# GeneralPurposePowerSupply.net
KiCad netlist of a schematic drawn in Altium Designer
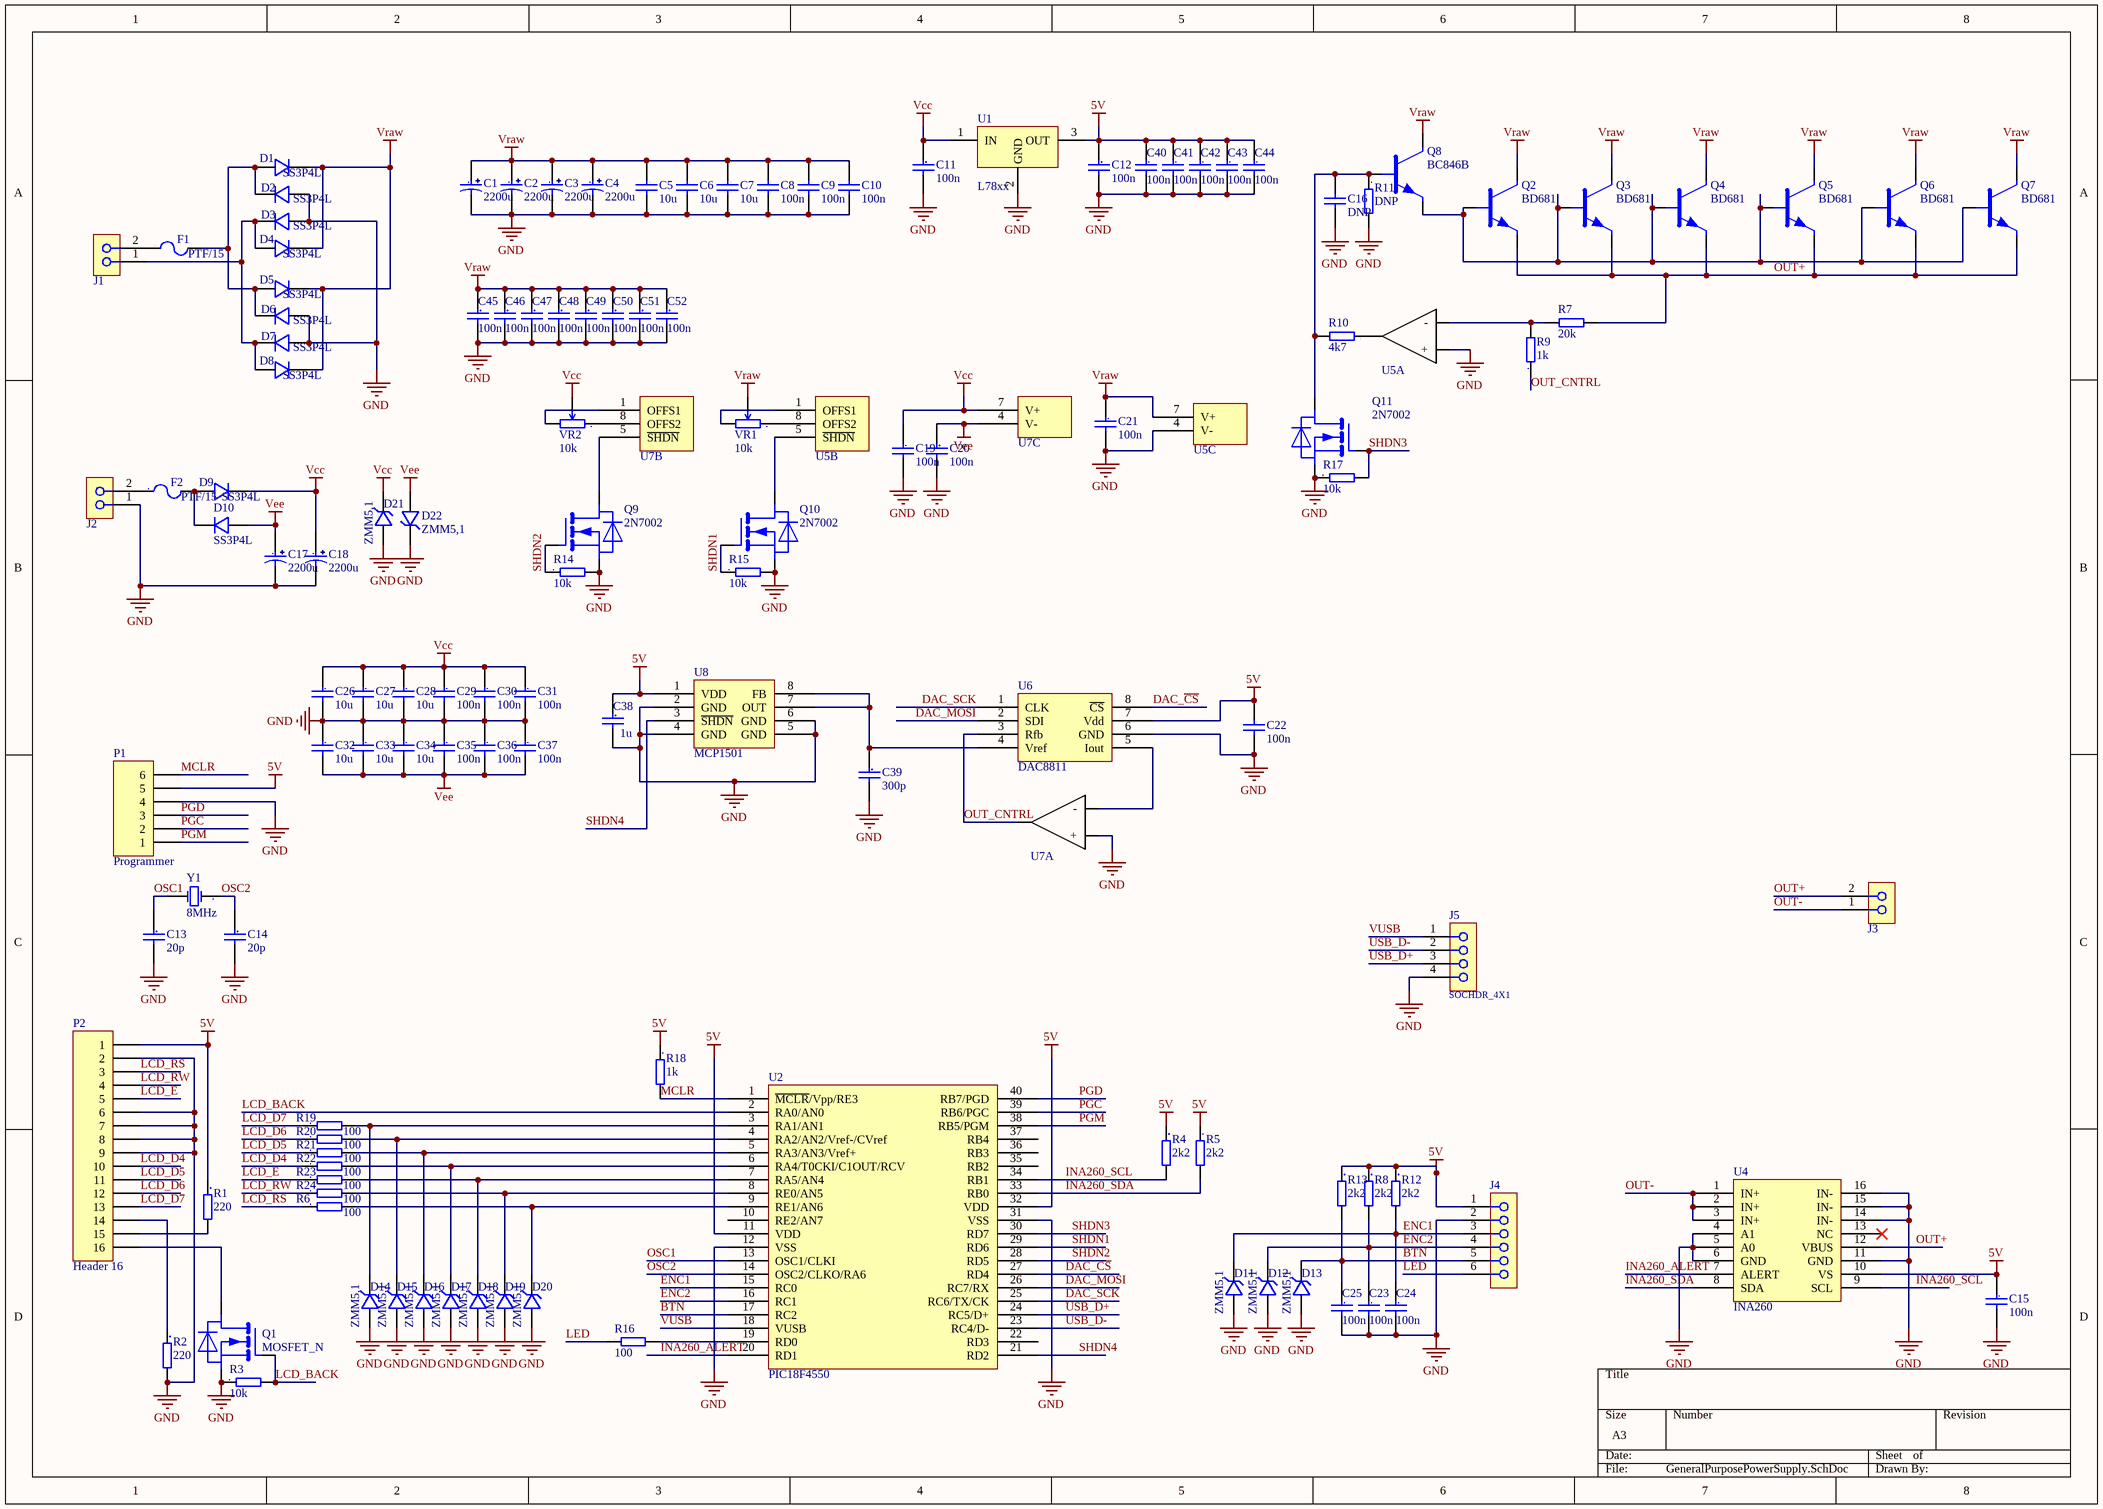
[diagram p0: GeneralPurposePowerSupply.SchDoc]

(export (version "E")
  (design (tool "Eeschema 10.0.6"))
  (components
    (comp (ref "C1") (value "2200u") (footprint "C_16x32") (libsource (lib "MyLib") (part "CAP_POL")))
    (comp (ref "C2") (value "2200u") (footprint "C_16x32") (libsource (lib "MyLib") (part "CAP_POL")))
    (comp (ref "C3") (value "2200u") (footprint "C_16x32") (libsource (lib "MyLib") (part "CAP_POL")))
    (comp (ref "C4") (value "2200u") (footprint "C_16x32") (libsource (lib "MyLib") (part "CAP_POL")))
    (comp (ref "C5") (value "10u") (footprint "C0805_N") (libsource (lib "MyLib") (part "CAP")))
    (comp (ref "C6") (value "10u") (footprint "C0805_N") (libsource (lib "MyLib") (part "CAP")))
    (comp (ref "C7") (value "10u") (footprint "C0805_N") (libsource (lib "MyLib") (part "CAP")))
    (comp (ref "C8") (value "100n") (footprint "C0603_N") (libsource (lib "MyLib") (part "CAP")))
    (comp (ref "C9") (value "100n") (footprint "C0603_N") (libsource (lib "MyLib") (part "CAP")))
    (comp (ref "C10") (value "100n") (footprint "C0603_N") (libsource (lib "MyLib") (part "CAP")))
    (comp (ref "C11") (value "100n") (footprint "C0603_N") (libsource (lib "MyLib") (part "CAP")))
    (comp (ref "C12") (value "100n") (footprint "C0603_N") (libsource (lib "MyLib") (part "CAP")))
    (comp (ref "C13") (value "20p") (footprint "C0603_N") (libsource (lib "MyLib") (part "CAP")))
    (comp (ref "C14") (value "20p") (footprint "C0603_N") (libsource (lib "MyLib") (part "CAP")))
    (comp (ref "C15") (value "100n") (footprint "C0603_N") (libsource (lib "MyLib") (part "CAP")))
    (comp (ref "C16") (value "DNP") (footprint "C0603_N") (libsource (lib "MyLib") (part "CAP")))
    (comp (ref "C17") (value "2200u") (footprint "C_16x32") (libsource (lib "MyLib") (part "CAP_POL")))
    (comp (ref "C18") (value "2200u") (footprint "C_16x32") (libsource (lib "MyLib") (part "CAP_POL")))
    (comp (ref "C19") (value "100n") (footprint "C0603_N") (libsource (lib "MyLib") (part "CAP")))
    (comp (ref "C20") (value "100n") (footprint "C0603_N") (libsource (lib "MyLib") (part "CAP")))
    (comp (ref "C21") (value "100n") (footprint "C0603_N") (libsource (lib "MyLib") (part "CAP")))
    (comp (ref "C22") (value "100n") (footprint "C0603_N") (libsource (lib "MyLib") (part "CAP")))
    (comp (ref "C23") (value "100n") (footprint "C0603_N") (libsource (lib "MyLib") (part "CAP")))
    (comp (ref "C24") (value "100n") (footprint "C0603_N") (libsource (lib "MyLib") (part "CAP")))
    (comp (ref "C25") (value "100n") (footprint "C0603_N") (libsource (lib "MyLib") (part "CAP")))
    (comp (ref "C26") (value "10u") (footprint "C0805_N") (libsource (lib "MyLib") (part "CAP")))
    (comp (ref "C27") (value "10u") (footprint "C0805_N") (libsource (lib "MyLib") (part "CAP")))
    (comp (ref "C28") (value "10u") (footprint "C0805_N") (libsource (lib "MyLib") (part "CAP")))
    (comp (ref "C29") (value "100n") (footprint "C0603_N") (libsource (lib "MyLib") (part "CAP")))
    (comp (ref "C30") (value "100n") (footprint "C0603_N") (libsource (lib "MyLib") (part "CAP")))
    (comp (ref "C31") (value "100n") (footprint "C0603_N") (libsource (lib "MyLib") (part "CAP")))
    (comp (ref "C32") (value "10u") (footprint "C0805_N") (libsource (lib "MyLib") (part "CAP")))
    (comp (ref "C33") (value "10u") (footprint "C0805_N") (libsource (lib "MyLib") (part "CAP")))
    (comp (ref "C34") (value "10u") (footprint "C0805_N") (libsource (lib "MyLib") (part "CAP")))
    (comp (ref "C35") (value "100n") (footprint "C0603_N") (libsource (lib "MyLib") (part "CAP")))
    (comp (ref "C36") (value "100n") (footprint "C0603_N") (libsource (lib "MyLib") (part "CAP")))
    (comp (ref "C37") (value "100n") (footprint "C0603_N") (libsource (lib "MyLib") (part "CAP")))
    (comp (ref "C38") (value "1u") (footprint "C0603_N") (libsource (lib "MyLib") (part "CAP")))
    (comp (ref "C39") (value "300p") (footprint "C0603_N") (libsource (lib "MyLib") (part "CAP")))
    (comp (ref "C40") (value "100n") (footprint "C0603_N") (libsource (lib "MyLib") (part "CAP")))
    (comp (ref "C41") (value "100n") (footprint "C0603_N") (libsource (lib "MyLib") (part "CAP")))
    (comp (ref "C42") (value "100n") (footprint "C0603_N") (libsource (lib "MyLib") (part "CAP")))
    (comp (ref "C43") (value "100n") (footprint "C0603_N") (libsource (lib "MyLib") (part "CAP")))
    (comp (ref "C44") (value "100n") (footprint "C0603_N") (libsource (lib "MyLib") (part "CAP")))
    (comp (ref "C45") (value "100n") (footprint "C0603_N") (libsource (lib "MyLib") (part "CAP")))
    (comp (ref "C46") (value "100n") (footprint "C0603_N") (libsource (lib "MyLib") (part "CAP")))
    (comp (ref "C47") (value "100n") (footprint "C0603_N") (libsource (lib "MyLib") (part "CAP")))
    (comp (ref "C48") (value "100n") (footprint "C0603_N") (libsource (lib "MyLib") (part "CAP")))
    (comp (ref "C49") (value "100n") (footprint "C0603_N") (libsource (lib "MyLib") (part "CAP")))
    (comp (ref "C50") (value "100n") (footprint "C0603_N") (libsource (lib "MyLib") (part "CAP")))
    (comp (ref "C51") (value "100n") (footprint "C0603_N") (libsource (lib "MyLib") (part "CAP")))
    (comp (ref "C52") (value "100n") (footprint "C0603_N") (libsource (lib "MyLib") (part "CAP")))
    (comp (ref "D1") (value "SS3P4L") (footprint "TO-277") (libsource (lib "MyLib") (part "DIODE")))
    (comp (ref "D2") (value "SS3P4L") (footprint "TO-277") (libsource (lib "MyLib") (part "DIODE")))
    (comp (ref "D3") (value "SS3P4L") (footprint "TO-277") (libsource (lib "MyLib") (part "DIODE")))
    (comp (ref "D4") (value "SS3P4L") (footprint "TO-277") (libsource (lib "MyLib") (part "DIODE")))
    (comp (ref "D5") (value "SS3P4L") (footprint "TO-277") (libsource (lib "MyLib") (part "DIODE")))
    (comp (ref "D6") (value "SS3P4L") (footprint "TO-277") (libsource (lib "MyLib") (part "DIODE")))
    (comp (ref "D7") (value "SS3P4L") (footprint "TO-277") (libsource (lib "MyLib") (part "DIODE")))
    (comp (ref "D8") (value "SS3P4L") (footprint "TO-277") (libsource (lib "MyLib") (part "DIODE")))
    (comp (ref "D9") (value "SS3P4L") (footprint "TO-277") (libsource (lib "MyLib") (part "DIODE")))
    (comp (ref "D10") (value "SS3P4L") (footprint "TO-277") (libsource (lib "MyLib") (part "DIODE")))
    (comp (ref "D11") (value "ZMM5,1") (footprint "SOD-80") (libsource (lib "MyLib") (part "DIODE_ZENER")))
    (comp (ref "D12") (value "ZMM5,1") (footprint "SOD-80") (libsource (lib "MyLib") (part "DIODE_ZENER")))
    (comp (ref "D13") (value "ZMM5,1") (footprint "SOD-80") (libsource (lib "MyLib") (part "DIODE_ZENER")))
    (comp (ref "D14") (value "ZMM5,1") (footprint "SOD-80") (libsource (lib "MyLib") (part "DIODE_ZENER")))
    (comp (ref "D15") (value "ZMM5,1") (footprint "SOD-80") (libsource (lib "MyLib") (part "DIODE_ZENER")))
    (comp (ref "D16") (value "ZMM5,1") (footprint "SOD-80") (libsource (lib "MyLib") (part "DIODE_ZENER")))
    (comp (ref "D17") (value "ZMM5,1") (footprint "SOD-80") (libsource (lib "MyLib") (part "DIODE_ZENER")))
    (comp (ref "D18") (value "ZMM5,1") (footprint "SOD-80") (libsource (lib "MyLib") (part "DIODE_ZENER")))
    (comp (ref "D19") (value "ZMM5,1") (footprint "SOD-80") (libsource (lib "MyLib") (part "DIODE_ZENER")))
    (comp (ref "D20") (value "ZMM5,1") (footprint "SOD-80") (libsource (lib "MyLib") (part "DIODE_ZENER")))
    (comp (ref "D21") (value "ZMM5,1") (footprint "SOD-80") (libsource (lib "MyLib") (part "DIODE_ZENER")))
    (comp (ref "D22") (value "ZMM5,1") (footprint "SOD-80") (libsource (lib "MyLib") (part "DIODE_ZENER")))
    (comp (ref "F1") (value "PTF/15") (footprint "FUSE_PTF/15") (libsource (lib "MyLib") (part "FUSE")))
    (comp (ref "F2") (value "PTF/15") (footprint "FUSE_PTF/15") (libsource (lib "MyLib") (part "FUSE")))
    (comp (ref "J1")
      (value "~")
      (footprint "TERM_BLOCK_2x1")
      (description "Socket")
      (libsource (lib "MyLib") (part "SOCHDR_2X1"))
    )
    (comp (ref "J2")
      (value "~")
      (footprint "TERM_BLOCK_2x1")
      (description "Socket")
      (libsource (lib "MyLib") (part "SOCHDR_2X1"))
    )
    (comp (ref "J3")
      (value "~")
      (footprint "TERM_BLOCK_2x1")
      (description "Socket")
      (libsource (lib "") (part "SOCHDR_2X1_1"))
    )
    (comp (ref "J4")
      (value "~")
      (footprint "PINSOCK_6x1_THT")
      (description "Socket")
      (libsource (lib "MyLib") (part "SOCHDR_6X1"))
    )
    (comp (ref "J5")
      (value "SOCHDR_4X1")
      (footprint "PINSOCK_4x1_THT")
      (description "Socket")
      (libsource (lib "MyLib") (part "SOCHDR_4X1"))
    )
    (comp (ref "P1")
      (value "Programmer")
      (footprint "HDR1X6")
      (description "Header, 6-Pin")
      (fields (field (name "PUBLISHER") "Altium Limited"))
      (libsource (lib "Miscellaneous Connectors") (part "Header 6"))
    )
    (comp (ref "P2")
      (value "Header 16")
      (footprint "HDR1X16")
      (description "Header, 16-Pin")
      (fields (field (name "PUBLISHER") "Altium Limited"))
      (libsource (lib "Miscellaneous Connectors") (part "Header 16"))
    )
    (comp (ref "Q1") (value "MOSFET_N") (footprint "SOT23_123_N") (libsource (lib "MyLib") (part "MOSFET_N")))
    (comp (ref "Q2") (value "BD681") (footprint "TO-126") (libsource (lib "MyLib") (part "BJT_NPN")))
    (comp (ref "Q3") (value "BD681") (footprint "TO-126") (libsource (lib "MyLib") (part "BJT_NPN")))
    (comp (ref "Q4") (value "BD681") (footprint "TO-126") (libsource (lib "MyLib") (part "BJT_NPN")))
    (comp (ref "Q5") (value "BD681") (footprint "TO-126") (libsource (lib "MyLib") (part "BJT_NPN")))
    (comp (ref "Q6") (value "BD681") (footprint "TO-126") (libsource (lib "MyLib") (part "BJT_NPN")))
    (comp (ref "Q7") (value "BD681") (footprint "TO-126") (libsource (lib "MyLib") (part "BJT_NPN")))
    (comp (ref "Q8") (value "BC846B") (footprint "SOT23_123_N") (libsource (lib "MyLib") (part "BJT_NPN")))
    (comp (ref "Q9") (value "2N7002") (footprint "SOT23_123_N") (libsource (lib "MyLib") (part "MOSFET_N")))
    (comp (ref "Q10") (value "2N7002") (footprint "SOT23_123_N") (libsource (lib "MyLib") (part "MOSFET_N")))
    (comp (ref "Q11") (value "2N7002") (footprint "SOT23_123_N") (libsource (lib "MyLib") (part "MOSFET_N")))
    (comp (ref "R1") (value "220") (footprint "R0603_N") (libsource (lib "MyLib") (part "RES")))
    (comp (ref "R2") (value "220") (footprint "R0603_N") (libsource (lib "MyLib") (part "RES")))
    (comp (ref "R3") (value "10k") (footprint "R0603_N") (libsource (lib "MyLib") (part "RES")))
    (comp (ref "R4") (value "2k2") (footprint "R0603_N") (libsource (lib "MyLib") (part "RES")))
    (comp (ref "R5") (value "2k2") (footprint "R0603_N") (libsource (lib "MyLib") (part "RES")))
    (comp (ref "R6") (value "100") (footprint "R0603_N") (libsource (lib "MyLib") (part "RES")))
    (comp (ref "R7") (value "20k") (footprint "R0603_N") (libsource (lib "MyLib") (part "RES")))
    (comp (ref "R8") (value "2k2") (footprint "R0603_N") (libsource (lib "MyLib") (part "RES")))
    (comp (ref "R9") (value "1k") (footprint "R0603_N") (libsource (lib "MyLib") (part "RES")))
    (comp (ref "R10") (value "4k7") (footprint "R0603_N") (libsource (lib "MyLib") (part "RES")))
    (comp (ref "R11") (value "DNP") (footprint "R0603_N") (libsource (lib "MyLib") (part "RES")))
    (comp (ref "R12") (value "2k2") (footprint "R0603_N") (libsource (lib "MyLib") (part "RES")))
    (comp (ref "R13") (value "2k2") (footprint "R0603_N") (libsource (lib "MyLib") (part "RES")))
    (comp (ref "R14") (value "10k") (footprint "R0603_N") (libsource (lib "MyLib") (part "RES")))
    (comp (ref "R15") (value "10k") (footprint "R0603_N") (libsource (lib "MyLib") (part "RES")))
    (comp (ref "R16") (value "100") (footprint "R0603_N") (libsource (lib "MyLib") (part "RES")))
    (comp (ref "R17") (value "10k") (footprint "R0603_N") (libsource (lib "MyLib") (part "RES")))
    (comp (ref "R18") (value "1k") (footprint "R0603_N") (libsource (lib "MyLib") (part "RES")))
    (comp (ref "R19") (value "100") (footprint "R0603_N") (libsource (lib "MyLib") (part "RES")))
    (comp (ref "R20") (value "100") (footprint "R0603_N") (libsource (lib "MyLib") (part "RES")))
    (comp (ref "R21") (value "100") (footprint "R0603_N") (libsource (lib "MyLib") (part "RES")))
    (comp (ref "R22") (value "100") (footprint "R0603_N") (libsource (lib "MyLib") (part "RES")))
    (comp (ref "R23") (value "100") (footprint "R0603_N") (libsource (lib "MyLib") (part "RES")))
    (comp (ref "R24") (value "100") (footprint "R0603_N") (libsource (lib "MyLib") (part "RES")))
    (comp (ref "U1") (value "L78xx") (footprint "TO-220") (libsource (lib "MyLib") (part "L78xx")))
    (comp (ref "U2")
      (value "PIC18F4550")
      (footprint "DIP-40")
      (description "PIC18F4550 40 pin type")
      (libsource (lib "MyLib") (part "PIC18F4550_DIP40"))
    )
    (comp (ref "U4") (value "INA260") (footprint "TSSOP-16") (libsource (lib "MyLib") (part "INA260")))
    (comp (ref "U5") (value "LT1218") (footprint "SOIC-8") (libsource (lib "MyLib") (part "LT1218")))
    (comp (ref "U6")
      (value "DAC8811")
      (footprint "VSSOP-8")
      (description "16 bit, 3-wire SPI DAC")
      (libsource (lib "MyLib") (part "DAC8811"))
    )
    (comp (ref "U7") (value "LT1218") (footprint "SOIC-8") (libsource (lib "MyLib") (part "LT1218")))
    (comp (ref "U8")
      (value "MCP1501")
      (footprint "SOIC-8")
      (description "SOIC-8 Volatage reference")
      (libsource (lib "MyLib") (part "MCP1501"))
    )
    (comp (ref "VR1")
      (value "10k")
      (footprint "POT_3364W")
      (description "Mono")
      (libsource (lib "MyLib") (part "RES_POT_M"))
    )
    (comp (ref "VR2")
      (value "10k")
      (footprint "POT_3364W")
      (description "Mono")
      (libsource (lib "MyLib") (part "RES_POT_M"))
    )
    (comp (ref "Y1") (value "8MHz") (footprint "CRYSTAL_HC49/SMD") (libsource (lib "MyLib") (part "XTAL_12")))
  )
  (nets
    (net (code "1") (name "/BTN") (class "Default")
      (node (ref "C25") (pin "1") (pinfunction "1_1") (pintype "passive"))
      (node (ref "D13") (pin "C") (pinfunction "C_C") (pintype "passive"))
      (node (ref "J4") (pin "5") (pinfunction "5_5") (pintype "passive"))
      (node (ref "R13") (pin "2") (pinfunction "2_2") (pintype "passive"))
      (node (ref "U2") (pin "17") (pinfunction "RC2_17") (pintype "passive"))
    )
    (net (code "2") (name "/DAC_MOSI") (class "Default")
      (node (ref "U2") (pin "26") (pinfunction "RC7/RX_26") (pintype "passive"))
      (node (ref "U6") (pin "2") (pinfunction "SDI_2") (pintype "passive"))
    )
    (net (code "3") (name "/DAC_SCK") (class "Default")
      (node (ref "U2") (pin "25") (pinfunction "RC6/TX/CK_25") (pintype "passive"))
      (node (ref "U6") (pin "1") (pinfunction "CLK_1") (pintype "passive"))
    )
    (net (code "4") (name "/DAC_~{CS}") (class "Default")
      (node (ref "U2") (pin "27") (pinfunction "RD4_27") (pintype "passive"))
      (node (ref "U6") (pin "8") (pinfunction "~{CS}_8") (pintype "passive"))
    )
    (net (code "5") (name "/ENC1") (class "Default")
      (node (ref "C24") (pin "1") (pinfunction "1_1") (pintype "passive"))
      (node (ref "D11") (pin "C") (pinfunction "C_C") (pintype "passive"))
      (node (ref "J4") (pin "3") (pinfunction "3_3") (pintype "passive"))
      (node (ref "R12") (pin "2") (pinfunction "2_2") (pintype "passive"))
      (node (ref "U2") (pin "15") (pinfunction "RC0_15") (pintype "passive"))
    )
    (net (code "6") (name "/ENC2") (class "Default")
      (node (ref "C23") (pin "1") (pinfunction "1_1") (pintype "passive"))
      (node (ref "D12") (pin "C") (pinfunction "C_C") (pintype "passive"))
      (node (ref "J4") (pin "4") (pinfunction "4_4") (pintype "passive"))
      (node (ref "R8") (pin "2") (pinfunction "2_2") (pintype "passive"))
      (node (ref "U2") (pin "16") (pinfunction "RC1_16") (pintype "passive"))
    )
    (net (code "7") (name "/INA260_ALERT") (class "Default")
      (node (ref "U2") (pin "20") (pinfunction "RD1_20") (pintype "passive"))
      (node (ref "U4") (pin "7") (pinfunction "ALERT_7") (pintype "passive"))
    )
    (net (code "8") (name "/INA260_SCL") (class "Default")
      (node (ref "R4") (pin "2") (pinfunction "2_2") (pintype "passive"))
      (node (ref "U2") (pin "34") (pinfunction "RB1_34") (pintype "passive"))
      (node (ref "U4") (pin "9") (pinfunction "SCL_9") (pintype "passive"))
    )
    (net (code "9") (name "/INA260_SDA") (class "Default")
      (node (ref "R5") (pin "2") (pinfunction "2_2") (pintype "passive"))
      (node (ref "U2") (pin "33") (pinfunction "RB0_33") (pintype "passive"))
      (node (ref "U4") (pin "8") (pinfunction "SDA_8") (pintype "passive"))
    )
    (net (code "10") (name "/LCD_BACK") (class "Default")
      (node (ref "Q1") (pin "G") (pinfunction "G_G") (pintype "passive"))
      (node (ref "R3") (pin "2") (pinfunction "2_2") (pintype "passive"))
      (node (ref "U2") (pin "2") (pinfunction "RA0/AN0_2") (pintype "passive"))
    )
    (net (code "11") (name "/LCD_D4") (class "Default")
      (node (ref "P2") (pin "10") (pinfunction "10_10") (pintype "passive"))
      (node (ref "R22") (pin "1") (pinfunction "1_1") (pintype "passive"))
    )
    (net (code "12") (name "/LCD_D5") (class "Default")
      (node (ref "P2") (pin "11") (pinfunction "11_11") (pintype "passive"))
      (node (ref "R21") (pin "1") (pinfunction "1_1") (pintype "passive"))
    )
    (net (code "13") (name "/LCD_D6") (class "Default")
      (node (ref "P2") (pin "12") (pinfunction "12_12") (pintype "passive"))
      (node (ref "R20") (pin "1") (pinfunction "1_1") (pintype "passive"))
    )
    (net (code "14") (name "/LCD_D7") (class "Default")
      (node (ref "P2") (pin "13") (pinfunction "13_13") (pintype "passive"))
      (node (ref "R19") (pin "1") (pinfunction "1_1") (pintype "passive"))
    )
    (net (code "15") (name "/LCD_E") (class "Default")
      (node (ref "P2") (pin "5") (pinfunction "5_5") (pintype "passive"))
      (node (ref "R23") (pin "1") (pinfunction "1_1") (pintype "passive"))
    )
    (net (code "16") (name "/LCD_RS") (class "Default")
      (node (ref "P2") (pin "3") (pinfunction "3_3") (pintype "passive"))
      (node (ref "R6") (pin "1") (pinfunction "1_1") (pintype "passive"))
    )
    (net (code "17") (name "/LCD_RW") (class "Default")
      (node (ref "P2") (pin "4") (pinfunction "4_4") (pintype "passive"))
      (node (ref "R24") (pin "1") (pinfunction "1_1") (pintype "passive"))
    )
    (net (code "18") (name "/LED") (class "Default")
      (node (ref "J4") (pin "6") (pinfunction "6_6") (pintype "passive"))
      (node (ref "R16") (pin "1") (pinfunction "1_1") (pintype "passive"))
    )
    (net (code "19") (name "/MCLR") (class "Default")
      (node (ref "P1") (pin "6") (pinfunction "6_6") (pintype "passive"))
      (node (ref "R18") (pin "2") (pinfunction "2_2") (pintype "passive"))
      (node (ref "U2") (pin "1") (pinfunction "~{MCLR}/Vpp/RE3_1") (pintype "passive"))
    )
    (net (code "20") (name "/OSC1") (class "Default")
      (node (ref "C13") (pin "1") (pinfunction "1_1") (pintype "passive"))
      (node (ref "U2") (pin "13") (pinfunction "OSC1/CLKI_13") (pintype "passive"))
      (node (ref "Y1") (pin "2") (pinfunction "OSC2_2") (pintype "passive"))
    )
    (net (code "21") (name "/OSC2") (class "Default")
      (node (ref "C14") (pin "1") (pinfunction "1_1") (pintype "passive"))
      (node (ref "U2") (pin "14") (pinfunction "OSC2/CLKO/RA6_14") (pintype "passive"))
      (node (ref "Y1") (pin "1") (pinfunction "1_1") (pintype "passive"))
    )
    (net (code "22") (name "/OUT+") (class "Default")
      (node (ref "J3") (pin "2") (pinfunction "2_2") (pintype "passive"))
      (node (ref "Q2") (pin "E") (pinfunction "E_E") (pintype "passive"))
      (node (ref "Q3") (pin "E") (pinfunction "E_E") (pintype "passive"))
      (node (ref "Q4") (pin "E") (pinfunction "E_E") (pintype "passive"))
      (node (ref "Q5") (pin "E") (pinfunction "E_E") (pintype "passive"))
      (node (ref "Q6") (pin "E") (pinfunction "E_E") (pintype "passive"))
      (node (ref "Q7") (pin "E") (pinfunction "E_E") (pintype "passive"))
      (node (ref "R7") (pin "1") (pinfunction "1_1") (pintype "passive"))
      (node (ref "U4") (pin "12") (pinfunction "VBUS_12") (pintype "passive"))
    )
    (net (code "23") (name "/OUT-") (class "Default")
      (node (ref "J3") (pin "1") (pinfunction "1_1") (pintype "passive"))
      (node (ref "U4") (pin "1") (pinfunction "IN+_1") (pintype "passive"))
      (node (ref "U4") (pin "2") (pinfunction "IN+_2") (pintype "passive"))
      (node (ref "U4") (pin "3") (pinfunction "IN+_3") (pintype "passive"))
    )
    (net (code "24") (name "/OUT_CNTRL") (class "Default")
      (node (ref "R9") (pin "1") (pinfunction "1_1") (pintype "passive"))
      (node (ref "U6") (pin "3") (pinfunction "Rfb_3") (pintype "passive"))
      (node (ref "U7") (pin "6") (pinfunction "Out_6") (pintype "passive"))
    )
    (net (code "25") (name "/PGC") (class "Default")
      (node (ref "P1") (pin "2") (pinfunction "2_2") (pintype "passive"))
      (node (ref "U2") (pin "39") (pinfunction "RB6/PGC_39") (pintype "passive"))
    )
    (net (code "26") (name "/PGD") (class "Default")
      (node (ref "P1") (pin "3") (pinfunction "3_3") (pintype "passive"))
      (node (ref "U2") (pin "40") (pinfunction "RB7/PGD_40") (pintype "passive"))
    )
    (net (code "27") (name "/PGM") (class "Default")
      (node (ref "P1") (pin "1") (pinfunction "1_1") (pintype "passive"))
      (node (ref "U2") (pin "38") (pinfunction "RB5/PGM_38") (pintype "passive"))
    )
    (net (code "28") (name "/SHDN1") (class "Default")
      (node (ref "Q10") (pin "G") (pinfunction "G_G") (pintype "passive"))
      (node (ref "R15") (pin "1") (pinfunction "1_1") (pintype "passive"))
      (node (ref "U2") (pin "29") (pinfunction "RD6_29") (pintype "passive"))
    )
    (net (code "29") (name "/SHDN2") (class "Default")
      (node (ref "Q9") (pin "G") (pinfunction "G_G") (pintype "passive"))
      (node (ref "R14") (pin "1") (pinfunction "1_1") (pintype "passive"))
      (node (ref "U2") (pin "28") (pinfunction "RD5_28") (pintype "passive"))
    )
    (net (code "30") (name "/SHDN3") (class "Default")
      (node (ref "Q11") (pin "G") (pinfunction "G_G") (pintype "passive"))
      (node (ref "R17") (pin "2") (pinfunction "2_2") (pintype "passive"))
      (node (ref "U2") (pin "30") (pinfunction "RD7_30") (pintype "passive"))
    )
    (net (code "31") (name "/SHDN4") (class "Default")
      (node (ref "U2") (pin "21") (pinfunction "RD2_21") (pintype "passive"))
      (node (ref "U8") (pin "3") (pinfunction "~{SHDN}_3") (pintype "passive"))
    )
    (net (code "32") (name "/USB_D+") (class "Default")
      (node (ref "J5") (pin "3") (pinfunction "3_3") (pintype "passive"))
      (node (ref "U2") (pin "24") (pinfunction "RC5/D+_24") (pintype "passive"))
    )
    (net (code "33") (name "/USB_D-") (class "Default")
      (node (ref "J5") (pin "2") (pinfunction "2_2") (pintype "passive"))
      (node (ref "U2") (pin "23") (pinfunction "RC4/D-_23") (pintype "passive"))
    )
    (net (code "34") (name "/VUSB") (class "Default")
      (node (ref "J5") (pin "1") (pinfunction "1_1") (pintype "passive"))
      (node (ref "U2") (pin "18") (pinfunction "VUSB_18") (pintype "passive"))
    )
    (net (code "35") (name "5V") (class "Default")
      (node (ref "C12") (pin "1") (pinfunction "1_1") (pintype "passive"))
      (node (ref "C15") (pin "1") (pinfunction "1_1") (pintype "passive"))
      (node (ref "C22") (pin "1") (pinfunction "1_1") (pintype "passive"))
      (node (ref "C38") (pin "1") (pinfunction "1_1") (pintype "passive"))
      (node (ref "C40") (pin "1") (pinfunction "1_1") (pintype "passive"))
      (node (ref "C41") (pin "1") (pinfunction "1_1") (pintype "passive"))
      (node (ref "C42") (pin "1") (pinfunction "1_1") (pintype "passive"))
      (node (ref "C43") (pin "1") (pinfunction "1_1") (pintype "passive"))
      (node (ref "C44") (pin "1") (pinfunction "1_1") (pintype "passive"))
      (node (ref "J4") (pin "1") (pinfunction "1_1") (pintype "passive"))
      (node (ref "P1") (pin "5") (pinfunction "5_5") (pintype "passive"))
      (node (ref "P2") (pin "1") (pinfunction "1_1") (pintype "passive"))
      (node (ref "R1") (pin "1") (pinfunction "1_1") (pintype "passive"))
      (node (ref "R12") (pin "1") (pinfunction "1_1") (pintype "passive"))
      (node (ref "R13") (pin "1") (pinfunction "1_1") (pintype "passive"))
      (node (ref "R18") (pin "1") (pinfunction "1_1") (pintype "passive"))
      (node (ref "R4") (pin "1") (pinfunction "1_1") (pintype "passive"))
      (node (ref "R5") (pin "1") (pinfunction "1_1") (pintype "passive"))
      (node (ref "R8") (pin "1") (pinfunction "1_1") (pintype "passive"))
      (node (ref "U1") (pin "3") (pinfunction "OUT_3") (pintype "passive"))
      (node (ref "U2") (pin "11") (pinfunction "VDD_11") (pintype "passive"))
      (node (ref "U2") (pin "32") (pinfunction "VDD_32") (pintype "passive"))
      (node (ref "U4") (pin "10") (pinfunction "VS_10") (pintype "passive"))
      (node (ref "U6") (pin "7") (pinfunction "Vdd_7") (pintype "passive"))
      (node (ref "U8") (pin "1") (pinfunction "VDD_1") (pintype "passive"))
    )
    (net (code "36") (name "GND") (class "Default")
      (node (ref "C1") (pin "N") (pinfunction "N_N") (pintype "passive"))
      (node (ref "C10") (pin "2") (pinfunction "2_2") (pintype "passive"))
      (node (ref "C11") (pin "2") (pinfunction "2_2") (pintype "passive"))
      (node (ref "C12") (pin "2") (pinfunction "2_2") (pintype "passive"))
      (node (ref "C13") (pin "2") (pinfunction "2_2") (pintype "passive"))
      (node (ref "C14") (pin "2") (pinfunction "2_2") (pintype "passive"))
      (node (ref "C15") (pin "2") (pinfunction "2_2") (pintype "passive"))
      (node (ref "C16") (pin "2") (pinfunction "2_2") (pintype "passive"))
      (node (ref "C17") (pin "N") (pinfunction "N_N") (pintype "passive"))
      (node (ref "C18") (pin "N") (pinfunction "N_N") (pintype "passive"))
      (node (ref "C19") (pin "2") (pinfunction "2_2") (pintype "passive"))
      (node (ref "C2") (pin "N") (pinfunction "N_N") (pintype "passive"))
      (node (ref "C20") (pin "2") (pinfunction "2_2") (pintype "passive"))
      (node (ref "C21") (pin "2") (pinfunction "2_2") (pintype "passive"))
      (node (ref "C22") (pin "2") (pinfunction "2_2") (pintype "passive"))
      (node (ref "C23") (pin "2") (pinfunction "2_2") (pintype "passive"))
      (node (ref "C24") (pin "2") (pinfunction "2_2") (pintype "passive"))
      (node (ref "C25") (pin "2") (pinfunction "2_2") (pintype "passive"))
      (node (ref "C26") (pin "2") (pinfunction "2_2") (pintype "passive"))
      (node (ref "C27") (pin "2") (pinfunction "2_2") (pintype "passive"))
      (node (ref "C28") (pin "2") (pinfunction "2_2") (pintype "passive"))
      (node (ref "C29") (pin "2") (pinfunction "2_2") (pintype "passive"))
      (node (ref "C3") (pin "N") (pinfunction "N_N") (pintype "passive"))
      (node (ref "C30") (pin "2") (pinfunction "2_2") (pintype "passive"))
      (node (ref "C31") (pin "2") (pinfunction "2_2") (pintype "passive"))
      (node (ref "C32") (pin "1") (pinfunction "1_1") (pintype "passive"))
      (node (ref "C33") (pin "1") (pinfunction "1_1") (pintype "passive"))
      (node (ref "C34") (pin "1") (pinfunction "1_1") (pintype "passive"))
      (node (ref "C35") (pin "1") (pinfunction "1_1") (pintype "passive"))
      (node (ref "C36") (pin "1") (pinfunction "1_1") (pintype "passive"))
      (node (ref "C37") (pin "1") (pinfunction "1_1") (pintype "passive"))
      (node (ref "C38") (pin "2") (pinfunction "2_2") (pintype "passive"))
      (node (ref "C39") (pin "2") (pinfunction "2_2") (pintype "passive"))
      (node (ref "C4") (pin "N") (pinfunction "N_N") (pintype "passive"))
      (node (ref "C40") (pin "2") (pinfunction "2_2") (pintype "passive"))
      (node (ref "C41") (pin "2") (pinfunction "2_2") (pintype "passive"))
      (node (ref "C42") (pin "2") (pinfunction "2_2") (pintype "passive"))
      (node (ref "C43") (pin "2") (pinfunction "2_2") (pintype "passive"))
      (node (ref "C44") (pin "2") (pinfunction "2_2") (pintype "passive"))
      (node (ref "C45") (pin "2") (pinfunction "2_2") (pintype "passive"))
      (node (ref "C46") (pin "2") (pinfunction "2_2") (pintype "passive"))
      (node (ref "C47") (pin "2") (pinfunction "2_2") (pintype "passive"))
      (node (ref "C48") (pin "2") (pinfunction "2_2") (pintype "passive"))
      (node (ref "C49") (pin "2") (pinfunction "2_2") (pintype "passive"))
      (node (ref "C5") (pin "2") (pinfunction "2_2") (pintype "passive"))
      (node (ref "C50") (pin "2") (pinfunction "2_2") (pintype "passive"))
      (node (ref "C51") (pin "2") (pinfunction "2_2") (pintype "passive"))
      (node (ref "C52") (pin "2") (pinfunction "2_2") (pintype "passive"))
      (node (ref "C6") (pin "2") (pinfunction "2_2") (pintype "passive"))
      (node (ref "C7") (pin "2") (pinfunction "2_2") (pintype "passive"))
      (node (ref "C8") (pin "2") (pinfunction "2_2") (pintype "passive"))
      (node (ref "C9") (pin "2") (pinfunction "2_2") (pintype "passive"))
      (node (ref "D11") (pin "A") (pinfunction "A_A") (pintype "passive"))
      (node (ref "D12") (pin "A") (pinfunction "A_A") (pintype "passive"))
      (node (ref "D13") (pin "A") (pinfunction "A_A") (pintype "passive"))
      (node (ref "D14") (pin "A") (pinfunction "A_A") (pintype "passive"))
      (node (ref "D15") (pin "A") (pinfunction "A_A") (pintype "passive"))
      (node (ref "D16") (pin "A") (pinfunction "A_A") (pintype "passive"))
      (node (ref "D17") (pin "A") (pinfunction "A_A") (pintype "passive"))
      (node (ref "D18") (pin "A") (pinfunction "A_A") (pintype "passive"))
      (node (ref "D19") (pin "A") (pinfunction "A_A") (pintype "passive"))
      (node (ref "D2") (pin "A") (pinfunction "A_A") (pintype "passive"))
      (node (ref "D20") (pin "A") (pinfunction "A_A") (pintype "passive"))
      (node (ref "D21") (pin "A") (pinfunction "A_A") (pintype "passive"))
      (node (ref "D22") (pin "C") (pinfunction "C_C") (pintype "passive"))
      (node (ref "D3") (pin "A") (pinfunction "A_A") (pintype "passive"))
      (node (ref "D6") (pin "A") (pinfunction "A_A") (pintype "passive"))
      (node (ref "D7") (pin "A") (pinfunction "A_A") (pintype "passive"))
      (node (ref "J2") (pin "1") (pinfunction "1_1") (pintype "passive"))
      (node (ref "J4") (pin "2") (pinfunction "2_2") (pintype "passive"))
      (node (ref "J5") (pin "4") (pinfunction "4_4") (pintype "passive"))
      (node (ref "P1") (pin "4") (pinfunction "4_4") (pintype "passive"))
      (node (ref "P2") (pin "2") (pinfunction "2_2") (pintype "passive"))
      (node (ref "P2") (pin "6") (pinfunction "6_6") (pintype "passive"))
      (node (ref "P2") (pin "7") (pinfunction "7_7") (pintype "passive"))
      (node (ref "P2") (pin "8") (pinfunction "8_8") (pintype "passive"))
      (node (ref "P2") (pin "9") (pinfunction "9_9") (pintype "passive"))
      (node (ref "Q1") (pin "S") (pinfunction "S_S") (pintype "passive"))
      (node (ref "Q10") (pin "S") (pinfunction "S_S") (pintype "passive"))
      (node (ref "Q11") (pin "S") (pinfunction "S_S") (pintype "passive"))
      (node (ref "Q9") (pin "S") (pinfunction "S_S") (pintype "passive"))
      (node (ref "R11") (pin "2") (pinfunction "2_2") (pintype "passive"))
      (node (ref "R14") (pin "2") (pinfunction "2_2") (pintype "passive"))
      (node (ref "R15") (pin "2") (pinfunction "2_2") (pintype "passive"))
      (node (ref "R17") (pin "1") (pinfunction "1_1") (pintype "passive"))
      (node (ref "R2") (pin "2") (pinfunction "2_2") (pintype "passive"))
      (node (ref "R3") (pin "1") (pinfunction "1_1") (pintype "passive"))
      (node (ref "U1") (pin "2") (pinfunction "GND_2") (pintype "passive"))
      (node (ref "U2") (pin "12") (pinfunction "VSS_12") (pintype "passive"))
      (node (ref "U2") (pin "31") (pinfunction "VSS_31") (pintype "passive"))
      (node (ref "U4") (pin "11") (pinfunction "GND_11") (pintype "passive"))
      (node (ref "U4") (pin "14") (pinfunction "IN-_14") (pintype "passive"))
      (node (ref "U4") (pin "15") (pinfunction "IN-_15") (pintype "passive"))
      (node (ref "U4") (pin "16") (pinfunction "IN-_16") (pintype "passive"))
      (node (ref "U4") (pin "4") (pinfunction "A1_4") (pintype "passive"))
      (node (ref "U4") (pin "5") (pinfunction "A0_5") (pintype "passive"))
      (node (ref "U4") (pin "6") (pinfunction "GND_6") (pintype "passive"))
      (node (ref "U5") (pin "3") (pinfunction "+_3") (pintype "passive"))
      (node (ref "U5") (pin "4") (pinfunction "V-_4") (pintype "passive"))
      (node (ref "U6") (pin "6") (pinfunction "GND_6") (pintype "passive"))
      (node (ref "U7") (pin "3") (pinfunction "+_3") (pintype "passive"))
      (node (ref "U8") (pin "2") (pinfunction "GND_2") (pintype "passive"))
      (node (ref "U8") (pin "4") (pinfunction "GND_4") (pintype "passive"))
      (node (ref "U8") (pin "5") (pinfunction "GND_5") (pintype "passive"))
      (node (ref "U8") (pin "6") (pinfunction "GND_6") (pintype "passive"))
    )
    (net (code "37") (name "Net-(C16-Pad1)") (class "Default")
      (node (ref "C16") (pin "1") (pinfunction "1_1") (pintype "passive"))
      (node (ref "Q11") (pin "D") (pinfunction "D_D") (pintype "passive"))
      (node (ref "Q8") (pin "B") (pinfunction "B_B") (pintype "passive"))
      (node (ref "R10") (pin "2") (pinfunction "2_2") (pintype "passive"))
      (node (ref "R11") (pin "1") (pinfunction "1_1") (pintype "passive"))
    )
    (net (code "38") (name "Net-(D1-PadA)") (class "Default")
      (node (ref "D1") (pin "A") (pinfunction "A_A") (pintype "passive"))
      (node (ref "D2") (pin "C") (pinfunction "C_C") (pintype "passive"))
      (node (ref "D5") (pin "A") (pinfunction "A_A") (pintype "passive"))
      (node (ref "D6") (pin "C") (pinfunction "C_C") (pintype "passive"))
      (node (ref "F1") (pin "2") (pinfunction "2_2") (pintype "passive"))
    )
    (net (code "39") (name "Net-(D3-PadC)") (class "Default")
      (node (ref "D3") (pin "C") (pinfunction "C_C") (pintype "passive"))
      (node (ref "D4") (pin "A") (pinfunction "A_A") (pintype "passive"))
      (node (ref "D7") (pin "C") (pinfunction "C_C") (pintype "passive"))
      (node (ref "D8") (pin "A") (pinfunction "A_A") (pintype "passive"))
      (node (ref "J1") (pin "1") (pinfunction "1_1") (pintype "passive"))
    )
    (net (code "40") (name "Net-(D10-PadC)") (class "Default")
      (node (ref "D10") (pin "C") (pinfunction "C_C") (pintype "passive"))
      (node (ref "D9") (pin "A") (pinfunction "A_A") (pintype "passive"))
      (node (ref "F2") (pin "2") (pinfunction "2_2") (pintype "passive"))
    )
    (net (code "41") (name "Net-(F1-Pad1)") (class "Default")
      (node (ref "F1") (pin "1") (pinfunction "1_1") (pintype "passive"))
      (node (ref "J1") (pin "2") (pinfunction "2_2") (pintype "passive"))
    )
    (net (code "42") (name "Net-(F2-Pad1)") (class "Default")
      (node (ref "F2") (pin "1") (pinfunction "1_1") (pintype "passive"))
      (node (ref "J2") (pin "2") (pinfunction "2_2") (pintype "passive"))
    )
    (net (code "43") (name "Net-(P2-Pad14)") (class "Default")
      (node (ref "P2") (pin "14") (pinfunction "14_14") (pintype "passive"))
      (node (ref "R2") (pin "1") (pinfunction "1_1") (pintype "passive"))
    )
    (net (code "44") (name "Net-(P2-Pad15)") (class "Default")
      (node (ref "P2") (pin "15") (pinfunction "15_15") (pintype "passive"))
      (node (ref "R1") (pin "2") (pinfunction "2_2") (pintype "passive"))
    )
    (net (code "45") (name "Net-(P2-Pad16)") (class "Default")
      (node (ref "P2") (pin "16") (pinfunction "16_16") (pintype "passive"))
      (node (ref "Q1") (pin "D") (pinfunction "D_D") (pintype "passive"))
    )
    (net (code "46") (name "Net-(Q2-PadB)") (class "Default")
      (node (ref "Q2") (pin "B") (pinfunction "B_B") (pintype "passive"))
      (node (ref "Q3") (pin "B") (pinfunction "B_B") (pintype "passive"))
      (node (ref "Q4") (pin "B") (pinfunction "B_B") (pintype "passive"))
      (node (ref "Q5") (pin "B") (pinfunction "B_B") (pintype "passive"))
      (node (ref "Q6") (pin "B") (pinfunction "B_B") (pintype "passive"))
      (node (ref "Q7") (pin "B") (pinfunction "B_B") (pintype "passive"))
      (node (ref "Q8") (pin "E") (pinfunction "E_E") (pintype "passive"))
    )
    (net (code "47") (name "Net-(U2-RA1{slash}AN1)") (class "Default")
      (node (ref "D14") (pin "C") (pinfunction "C_C") (pintype "passive"))
      (node (ref "R19") (pin "2") (pinfunction "2_2") (pintype "passive"))
      (node (ref "U2") (pin "3") (pinfunction "RA1/AN1_3") (pintype "passive"))
    )
    (net (code "48") (name "Net-(U2-RA2{slash}AN2{slash}Vref-{slash}CVref)") (class "Default")
      (node (ref "D15") (pin "C") (pinfunction "C_C") (pintype "passive"))
      (node (ref "R20") (pin "2") (pinfunction "2_2") (pintype "passive"))
      (node (ref "U2") (pin "4") (pinfunction "RA2/AN2/Vref-/CVref_4") (pintype "passive"))
    )
    (net (code "49") (name "Net-(U2-RA3{slash}AN3{slash}Vref+)") (class "Default")
      (node (ref "D16") (pin "C") (pinfunction "C_C") (pintype "passive"))
      (node (ref "R21") (pin "2") (pinfunction "2_2") (pintype "passive"))
      (node (ref "U2") (pin "5") (pinfunction "RA3/AN3/Vref+_5") (pintype "passive"))
    )
    (net (code "50") (name "Net-(U2-RA4{slash}T0CKI{slash}C1OUT{slash}RCV)") (class "Default")
      (node (ref "D17") (pin "C") (pinfunction "C_C") (pintype "passive"))
      (node (ref "R22") (pin "2") (pinfunction "2_2") (pintype "passive"))
      (node (ref "U2") (pin "6") (pinfunction "RA4/T0CKI/C1OUT/RCV_6") (pintype "passive"))
    )
    (net (code "51") (name "Net-(U2-RA5{slash}AN4)") (class "Default")
      (node (ref "D18") (pin "C") (pinfunction "C_C") (pintype "passive"))
      (node (ref "R23") (pin "2") (pinfunction "2_2") (pintype "passive"))
      (node (ref "U2") (pin "7") (pinfunction "RA5/AN4_7") (pintype "passive"))
    )
    (net (code "52") (name "Net-(U2-RD0)") (class "Default")
      (node (ref "R16") (pin "2") (pinfunction "2_2") (pintype "passive"))
      (node (ref "U2") (pin "19") (pinfunction "RD0_19") (pintype "passive"))
    )
    (net (code "53") (name "Net-(U2-RE0{slash}AN5)") (class "Default")
      (node (ref "D19") (pin "C") (pinfunction "C_C") (pintype "passive"))
      (node (ref "R24") (pin "2") (pinfunction "2_2") (pintype "passive"))
      (node (ref "U2") (pin "8") (pinfunction "RE0/AN5_8") (pintype "passive"))
    )
    (net (code "54") (name "Net-(U2-RE1{slash}AN6)") (class "Default")
      (node (ref "D20") (pin "C") (pinfunction "C_C") (pintype "passive"))
      (node (ref "R6") (pin "2") (pinfunction "2_2") (pintype "passive"))
      (node (ref "U2") (pin "9") (pinfunction "RE1/AN6_9") (pintype "passive"))
    )
    (net (code "55") (name "Net-(U5A--)") (class "Default")
      (node (ref "R7") (pin "2") (pinfunction "2_2") (pintype "passive"))
      (node (ref "R9") (pin "2") (pinfunction "2_2") (pintype "passive"))
      (node (ref "U5") (pin "2") (pinfunction "-_2") (pintype "passive"))
    )
    (net (code "56") (name "Net-(U5A-Out)") (class "Default")
      (node (ref "R10") (pin "1") (pinfunction "1_1") (pintype "passive"))
      (node (ref "U5") (pin "6") (pinfunction "Out_6") (pintype "passive"))
    )
    (net (code "57") (name "Net-(U5B-OFFS1)") (class "Default")
      (node (ref "U5") (pin "1") (pinfunction "OFFS1_1") (pintype "passive"))
      (node (ref "VR1") (pin "CW") (pinfunction "CW_CW") (pintype "passive"))
    )
    (net (code "58") (name "Net-(U5B-OFFS2)") (class "Default")
      (node (ref "U5") (pin "8") (pinfunction "OFFS2_8") (pintype "passive"))
      (node (ref "VR1") (pin "CCW") (pinfunction "CCW_CCW") (pintype "passive"))
    )
    (net (code "59") (name "Net-(U5B-~{SHDN})") (class "Default")
      (node (ref "Q10") (pin "D") (pinfunction "D_D") (pintype "passive"))
      (node (ref "U5") (pin "5") (pinfunction "~{SHDN}_5") (pintype "passive"))
    )
    (net (code "60") (name "Net-(U6-Iout)") (class "Default")
      (node (ref "U6") (pin "5") (pinfunction "Iout_5") (pintype "passive"))
      (node (ref "U7") (pin "2") (pinfunction "-_2") (pintype "passive"))
    )
    (net (code "61") (name "Net-(U6-Vref)") (class "Default")
      (node (ref "C39") (pin "1") (pinfunction "1_1") (pintype "passive"))
      (node (ref "U6") (pin "4") (pinfunction "Vref_4") (pintype "passive"))
      (node (ref "U8") (pin "7") (pinfunction "OUT_7") (pintype "passive"))
      (node (ref "U8") (pin "8") (pinfunction "FB_8") (pintype "passive"))
    )
    (net (code "62") (name "Net-(U7B-OFFS1)") (class "Default")
      (node (ref "U7") (pin "1") (pinfunction "OFFS1_1") (pintype "passive"))
      (node (ref "VR2") (pin "CW") (pinfunction "CW_CW") (pintype "passive"))
    )
    (net (code "63") (name "Net-(U7B-OFFS2)") (class "Default")
      (node (ref "U7") (pin "8") (pinfunction "OFFS2_8") (pintype "passive"))
      (node (ref "VR2") (pin "CCW") (pinfunction "CCW_CCW") (pintype "passive"))
    )
    (net (code "64") (name "Net-(U7B-~{SHDN})") (class "Default")
      (node (ref "Q9") (pin "D") (pinfunction "D_D") (pintype "passive"))
      (node (ref "U7") (pin "5") (pinfunction "~{SHDN}_5") (pintype "passive"))
    )
    (net (code "65") (name "Vcc") (class "Default")
      (node (ref "C11") (pin "1") (pinfunction "1_1") (pintype "passive"))
      (node (ref "C18") (pin "P") (pinfunction "P_P") (pintype "passive"))
      (node (ref "C19") (pin "1") (pinfunction "1_1") (pintype "passive"))
      (node (ref "C26") (pin "1") (pinfunction "1_1") (pintype "passive"))
      (node (ref "C27") (pin "1") (pinfunction "1_1") (pintype "passive"))
      (node (ref "C28") (pin "1") (pinfunction "1_1") (pintype "passive"))
      (node (ref "C29") (pin "1") (pinfunction "1_1") (pintype "passive"))
      (node (ref "C30") (pin "1") (pinfunction "1_1") (pintype "passive"))
      (node (ref "C31") (pin "1") (pinfunction "1_1") (pintype "passive"))
      (node (ref "D21") (pin "C") (pinfunction "C_C") (pintype "passive"))
      (node (ref "D9") (pin "C") (pinfunction "C_C") (pintype "passive"))
      (node (ref "U1") (pin "1") (pinfunction "IN_1") (pintype "passive"))
      (node (ref "U7") (pin "7") (pinfunction "V+_7") (pintype "passive"))
      (node (ref "VR2") (pin "WIPER") (pinfunction "WIPER_WIPER") (pintype "passive"))
    )
    (net (code "66") (name "Vee") (class "Default")
      (node (ref "C17") (pin "P") (pinfunction "P_P") (pintype "passive"))
      (node (ref "C20") (pin "1") (pinfunction "1_1") (pintype "passive"))
      (node (ref "C32") (pin "2") (pinfunction "2_2") (pintype "passive"))
      (node (ref "C33") (pin "2") (pinfunction "2_2") (pintype "passive"))
      (node (ref "C34") (pin "2") (pinfunction "2_2") (pintype "passive"))
      (node (ref "C35") (pin "2") (pinfunction "2_2") (pintype "passive"))
      (node (ref "C36") (pin "2") (pinfunction "2_2") (pintype "passive"))
      (node (ref "C37") (pin "2") (pinfunction "2_2") (pintype "passive"))
      (node (ref "D10") (pin "A") (pinfunction "A_A") (pintype "passive"))
      (node (ref "D22") (pin "A") (pinfunction "A_A") (pintype "passive"))
      (node (ref "U7") (pin "4") (pinfunction "V-_4") (pintype "passive"))
    )
    (net (code "67") (name "Vraw") (class "Default")
      (node (ref "C1") (pin "P") (pinfunction "P_P") (pintype "passive"))
      (node (ref "C10") (pin "1") (pinfunction "1_1") (pintype "passive"))
      (node (ref "C2") (pin "P") (pinfunction "P_P") (pintype "passive"))
      (node (ref "C21") (pin "1") (pinfunction "1_1") (pintype "passive"))
      (node (ref "C3") (pin "P") (pinfunction "P_P") (pintype "passive"))
      (node (ref "C4") (pin "P") (pinfunction "P_P") (pintype "passive"))
      (node (ref "C45") (pin "1") (pinfunction "1_1") (pintype "passive"))
      (node (ref "C46") (pin "1") (pinfunction "1_1") (pintype "passive"))
      (node (ref "C47") (pin "1") (pinfunction "1_1") (pintype "passive"))
      (node (ref "C48") (pin "1") (pinfunction "1_1") (pintype "passive"))
      (node (ref "C49") (pin "1") (pinfunction "1_1") (pintype "passive"))
      (node (ref "C5") (pin "1") (pinfunction "1_1") (pintype "passive"))
      (node (ref "C50") (pin "1") (pinfunction "1_1") (pintype "passive"))
      (node (ref "C51") (pin "1") (pinfunction "1_1") (pintype "passive"))
      (node (ref "C52") (pin "1") (pinfunction "1_1") (pintype "passive"))
      (node (ref "C6") (pin "1") (pinfunction "1_1") (pintype "passive"))
      (node (ref "C7") (pin "1") (pinfunction "1_1") (pintype "passive"))
      (node (ref "C8") (pin "1") (pinfunction "1_1") (pintype "passive"))
      (node (ref "C9") (pin "1") (pinfunction "1_1") (pintype "passive"))
      (node (ref "D1") (pin "C") (pinfunction "C_C") (pintype "passive"))
      (node (ref "D4") (pin "C") (pinfunction "C_C") (pintype "passive"))
      (node (ref "D5") (pin "C") (pinfunction "C_C") (pintype "passive"))
      (node (ref "D8") (pin "C") (pinfunction "C_C") (pintype "passive"))
      (node (ref "Q2") (pin "C") (pinfunction "C_C") (pintype "passive"))
      (node (ref "Q3") (pin "C") (pinfunction "C_C") (pintype "passive"))
      (node (ref "Q4") (pin "C") (pinfunction "C_C") (pintype "passive"))
      (node (ref "Q5") (pin "C") (pinfunction "C_C") (pintype "passive"))
      (node (ref "Q6") (pin "C") (pinfunction "C_C") (pintype "passive"))
      (node (ref "Q7") (pin "C") (pinfunction "C_C") (pintype "passive"))
      (node (ref "Q8") (pin "C") (pinfunction "C_C") (pintype "passive"))
      (node (ref "U5") (pin "7") (pinfunction "V+_7") (pintype "passive"))
      (node (ref "VR1") (pin "WIPER") (pinfunction "WIPER_WIPER") (pintype "passive"))
    )
    (net (code "68") (name "unconnected-(U2-RB2-Pad35)") (class "Default")
      (node (ref "U2") (pin "35") (pinfunction "RB2_35") (pintype "passive"))
    )
    (net (code "69") (name "unconnected-(U2-RB3-Pad36)") (class "Default")
      (node (ref "U2") (pin "36") (pinfunction "RB3_36") (pintype "passive"))
    )
    (net (code "70") (name "unconnected-(U2-RB4-Pad37)") (class "Default")
      (node (ref "U2") (pin "37") (pinfunction "RB4_37") (pintype "passive"))
    )
    (net (code "71") (name "unconnected-(U2-RD3-Pad22)") (class "Default")
      (node (ref "U2") (pin "22") (pinfunction "RD3_22") (pintype "passive"))
    )
    (net (code "72") (name "unconnected-(U2-RE2{slash}AN7-Pad10)") (class "Default")
      (node (ref "U2") (pin "10") (pinfunction "RE2/AN7_10") (pintype "passive"))
    )
    (net (code "73") (name "unconnected-(U4-NC-Pad13)") (class "Default")
      (node (ref "U4") (pin "13") (pinfunction "NC_13") (pintype "passive+no_connect"))
    )
  )
)
